# WifiNode_Per.net
KiCad netlist of a schematic drawn in Altium Designer
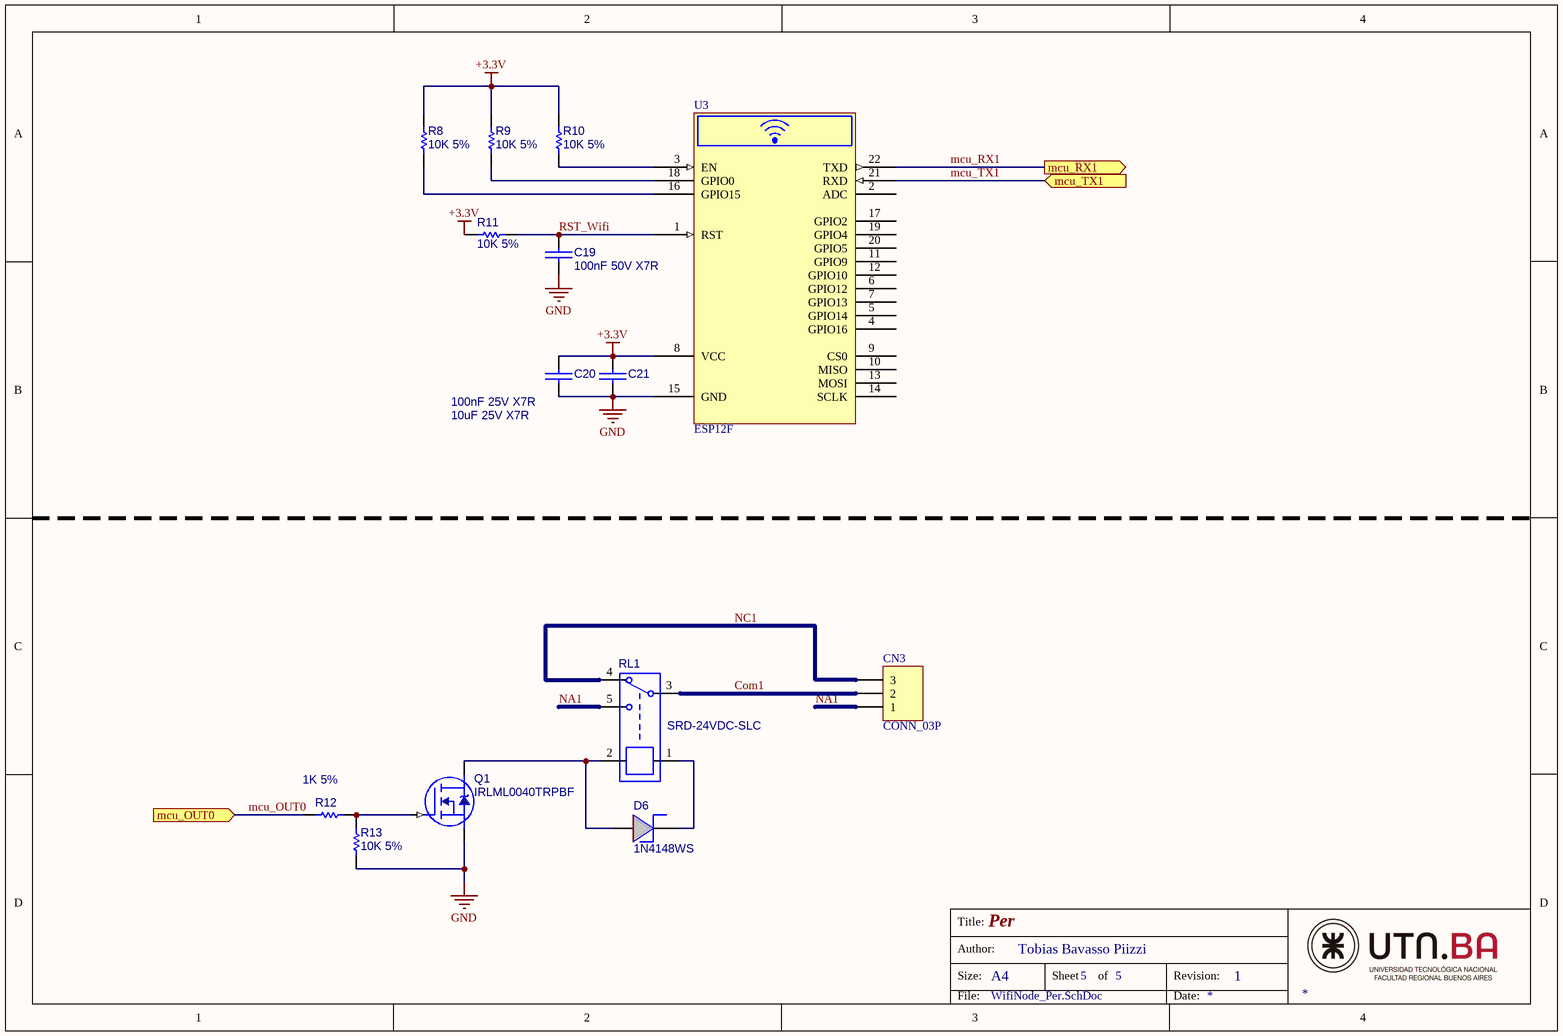
[diagram p0: WifiNode_Per.SchDoc]

(export (version "E")
  (design (tool "Eeschema 10.0.6"))
  (components
    (comp (ref "C19")
      (value "100nF 50V X7R")
      (footprint "C_0805")
      (description "Non Polarized Capacitor")
      (libsource (lib "WifiNode") (part "CAP"))
    )
    (comp (ref "C20")
      (value "100nF 25V X7R")
      (footprint "C_0805")
      (description "Non Polarized Capacitor")
      (libsource (lib "WifiNode") (part "CAP"))
    )
    (comp (ref "C21")
      (value "10uF 25V X7R")
      (footprint "C_0805")
      (description "Non Polarized Capacitor")
      (libsource (lib "WifiNode") (part "CAP"))
    )
    (comp (ref "CN3")
      (value "CONN_03P")
      (footprint "TerminalBlock_1x3_P5mm")
      (description "Connector Generic 3 Vias")
      (libsource (lib "WifiNode") (part "CONN_03P"))
    )
    (comp (ref "D6")
      (value "1N4148WS")
      (footprint "D_SMA")
      (description "Diode Shottky")
      (libsource (lib "WifiNode") (part "DIODO_SH"))
    )
    (comp (ref "Q1")
      (value "IRLML0040TRPBF")
      (footprint "SOT_23")
      (description "Mosfet N-Ch")
      (libsource (lib "WifiNode") (part "N_MOSFET_SOT23"))
    )
    (comp (ref "R8")
      (value "10K 5%")
      (footprint "R_0805")
      (description "Resistor")
      (libsource (lib "WifiNode") (part "Res1"))
    )
    (comp (ref "R9")
      (value "10K 5%")
      (footprint "R_0805")
      (description "Resistor")
      (libsource (lib "WifiNode") (part "Res1"))
    )
    (comp (ref "R10")
      (value "10K 5%")
      (footprint "R_0805")
      (description "Resistor")
      (libsource (lib "WifiNode") (part "Res1"))
    )
    (comp (ref "R11")
      (value "10K 5%")
      (footprint "R_0805")
      (description "Resistor")
      (libsource (lib "WifiNode") (part "Res1"))
    )
    (comp (ref "R12")
      (value "1K 5%")
      (footprint "R_0805")
      (description "Resistor")
      (libsource (lib "WifiNode") (part "Res1"))
    )
    (comp (ref "R13")
      (value "10K 5%")
      (footprint "R_0805")
      (description "Resistor")
      (libsource (lib "WifiNode") (part "Res1"))
    )
    (comp (ref "RL1")
      (value "SRD-24VDC-SLC")
      (footprint "943-1C")
      (description "Relay SPDT")
      (libsource (lib "WifiNode") (part "RELAY SPDT"))
    )
    (comp (ref "U3")
      (value "ESP12F")
      (footprint "ESP12F")
      (description "Wifi Module")
      (libsource (lib "WifiNode") (part "ESP12F Wifi Module"))
    )
  )
  (nets
    (net (code "1") (name "+3.3V") (class "Default")
      (node (ref "C20") (pin "1") (pinfunction "1_1") (pintype "passive"))
      (node (ref "C21") (pin "1") (pinfunction "1_1") (pintype "passive"))
      (node (ref "R10") (pin "2") (pinfunction "2_2") (pintype "passive"))
      (node (ref "R11") (pin "1") (pinfunction "1_1") (pintype "passive"))
      (node (ref "R8") (pin "2") (pinfunction "2_2") (pintype "passive"))
      (node (ref "R9") (pin "2") (pinfunction "2_2") (pintype "passive"))
      (node (ref "U3") (pin "8") (pinfunction "VCC_8") (pintype "power_in"))
    )
    (net (code "2") (name "/Com1") (class "Default")
      (node (ref "CN3") (pin "2") (pinfunction "2_2") (pintype "passive"))
      (node (ref "RL1") (pin "3") (pinfunction "3_3") (pintype "passive"))
    )
    (net (code "3") (name "/NA1") (class "Default")
      (node (ref "CN3") (pin "1") (pinfunction "1_1") (pintype "passive"))
      (node (ref "RL1") (pin "5") (pinfunction "5_5") (pintype "passive"))
    )
    (net (code "4") (name "/NC1") (class "Default")
      (node (ref "CN3") (pin "3") (pinfunction "3_3") (pintype "passive"))
      (node (ref "RL1") (pin "4") (pinfunction "4_4") (pintype "passive"))
    )
    (net (code "5") (name "/RST_Wifi") (class "Default")
      (node (ref "C19") (pin "1") (pinfunction "1_1") (pintype "passive"))
      (node (ref "R11") (pin "2") (pinfunction "2_2") (pintype "passive"))
      (node (ref "U3") (pin "1") (pinfunction "RST_1") (pintype "input"))
    )
    (net (code "6") (name "/mcu_OUT0") (class "Default")
      (node (ref "R12") (pin "2") (pinfunction "2_2") (pintype "passive"))
    )
    (net (code "7") (name "/mcu_RX1") (class "Default")
      (node (ref "U3") (pin "22") (pinfunction "TXD_22") (pintype "output"))
    )
    (net (code "8") (name "/mcu_TX1") (class "Default")
      (node (ref "U3") (pin "21") (pinfunction "RXD_21") (pintype "input"))
    )
    (net (code "9") (name "GND") (class "Default")
      (node (ref "C19") (pin "2") (pinfunction "2_2") (pintype "passive"))
      (node (ref "C20") (pin "2") (pinfunction "2_2") (pintype "passive"))
      (node (ref "C21") (pin "2") (pinfunction "2_2") (pintype "passive"))
      (node (ref "Q1") (pin "2") (pinfunction "SOURCE_2") (pintype "passive"))
      (node (ref "R13") (pin "1") (pinfunction "1_1") (pintype "passive"))
      (node (ref "U3") (pin "15") (pinfunction "GND_15") (pintype "power_in"))
    )
    (net (code "10") (name "Net-(D6-A)") (class "Default")
      (node (ref "D6") (pin "1") (pinfunction "A_1") (pintype "passive"))
      (node (ref "Q1") (pin "3") (pinfunction "DRAIN_3") (pintype "passive"))
      (node (ref "RL1") (pin "2") (pinfunction "2_2") (pintype "passive"))
    )
    (net (code "11") (name "Net-(D6-K)") (class "Default")
      (node (ref "D6") (pin "2") (pinfunction "K_2") (pintype "passive"))
      (node (ref "RL1") (pin "1") (pinfunction "1_1") (pintype "passive"))
    )
    (net (code "12") (name "Net-(Q1-GATE)") (class "Default")
      (node (ref "Q1") (pin "1") (pinfunction "GATE_1") (pintype "input"))
      (node (ref "R12") (pin "1") (pinfunction "1_1") (pintype "passive"))
      (node (ref "R13") (pin "2") (pinfunction "2_2") (pintype "passive"))
    )
    (net (code "13") (name "Net-(U3-EN)") (class "Default")
      (node (ref "R10") (pin "1") (pinfunction "1_1") (pintype "passive"))
      (node (ref "U3") (pin "3") (pinfunction "EN_3") (pintype "input"))
    )
    (net (code "14") (name "Net-(U3-GPIO0)") (class "Default")
      (node (ref "R9") (pin "1") (pinfunction "1_1") (pintype "passive"))
      (node (ref "U3") (pin "18") (pinfunction "GPIO0_18") (pintype "passive"))
    )
    (net (code "15") (name "Net-(U3-GPIO15)") (class "Default")
      (node (ref "R8") (pin "1") (pinfunction "1_1") (pintype "passive"))
      (node (ref "U3") (pin "16") (pinfunction "GPIO15_16") (pintype "passive"))
    )
    (net (code "16") (name "unconnected-(U3-ADC-Pad2)") (class "Default")
      (node (ref "U3") (pin "2") (pinfunction "ADC_2") (pintype "passive"))
    )
    (net (code "17") (name "unconnected-(U3-CS0-Pad9)") (class "Default")
      (node (ref "U3") (pin "9") (pinfunction "CS0_9") (pintype "passive"))
    )
    (net (code "18") (name "unconnected-(U3-GPIO2-Pad17)") (class "Default")
      (node (ref "U3") (pin "17") (pinfunction "GPIO2_17") (pintype "passive"))
    )
    (net (code "19") (name "unconnected-(U3-GPIO4-Pad19)") (class "Default")
      (node (ref "U3") (pin "19") (pinfunction "GPIO4_19") (pintype "passive"))
    )
    (net (code "20") (name "unconnected-(U3-GPIO5-Pad20)") (class "Default")
      (node (ref "U3") (pin "20") (pinfunction "GPIO5_20") (pintype "passive"))
    )
    (net (code "21") (name "unconnected-(U3-GPIO9-Pad11)") (class "Default")
      (node (ref "U3") (pin "11") (pinfunction "GPIO9_11") (pintype "passive"))
    )
    (net (code "22") (name "unconnected-(U3-GPIO10-Pad12)") (class "Default")
      (node (ref "U3") (pin "12") (pinfunction "GPIO10_12") (pintype "passive"))
    )
    (net (code "23") (name "unconnected-(U3-GPIO12-Pad6)") (class "Default")
      (node (ref "U3") (pin "6") (pinfunction "GPIO12_6") (pintype "passive"))
    )
    (net (code "24") (name "unconnected-(U3-GPIO13-Pad7)") (class "Default")
      (node (ref "U3") (pin "7") (pinfunction "GPIO13_7") (pintype "passive"))
    )
    (net (code "25") (name "unconnected-(U3-GPIO14-Pad5)") (class "Default")
      (node (ref "U3") (pin "5") (pinfunction "GPIO14_5") (pintype "passive"))
    )
    (net (code "26") (name "unconnected-(U3-GPIO16-Pad4)") (class "Default")
      (node (ref "U3") (pin "4") (pinfunction "GPIO16_4") (pintype "passive"))
    )
    (net (code "27") (name "unconnected-(U3-MISO-Pad10)") (class "Default")
      (node (ref "U3") (pin "10") (pinfunction "MISO_10") (pintype "passive"))
    )
    (net (code "28") (name "unconnected-(U3-MOSI-Pad13)") (class "Default")
      (node (ref "U3") (pin "13") (pinfunction "MOSI_13") (pintype "passive"))
    )
    (net (code "29") (name "unconnected-(U3-SCLK-Pad14)") (class "Default")
      (node (ref "U3") (pin "14") (pinfunction "SCLK_14") (pintype "passive"))
    )
  )
)
